# analog-out-and-pwr-amp.net
KiCad netlist of a schematic drawn in EAGLE
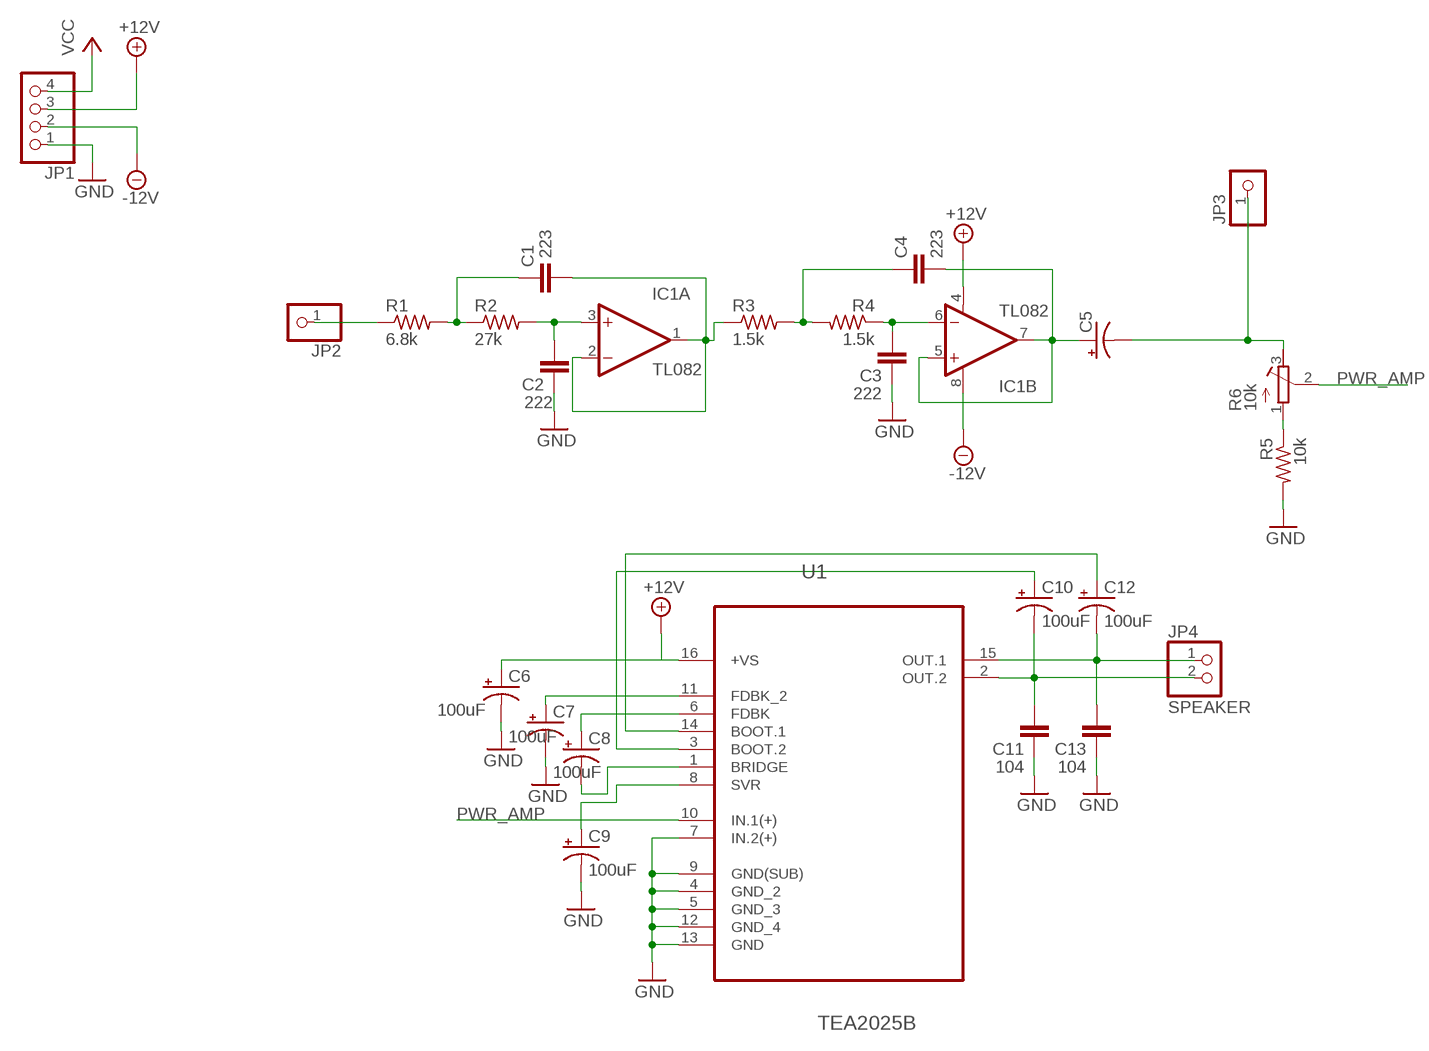
[diagram p0: schematic, sheet 1]

(export (version "E")
  (design (tool "Eeschema 10.0.6"))
  (components
    (comp (ref "C1")
      (value "223")
      (footprint "eagle-import:C025-060X050")
      (libsource (lib "eagle-import") (part "C-EUCERAMIC-CAP-COMMON"))
    )
    (comp (ref "C2")
      (value "222")
      (footprint "eagle-import:C025-060X050")
      (libsource (lib "eagle-import") (part "C-EUCERAMIC-CAP-COMMON"))
    )
    (comp (ref "C3")
      (value "222")
      (footprint "eagle-import:C025-060X050")
      (libsource (lib "eagle-import") (part "C-EUCERAMIC-CAP-COMMON"))
    )
    (comp (ref "C4")
      (value "223")
      (footprint "eagle-import:C025-060X050")
      (libsource (lib "eagle-import") (part "C-EUCERAMIC-CAP-COMMON"))
    )
    (comp (ref "C5")
      (value "CPOL-USSANYO_D")
      (footprint "eagle-import:POL-CAP-COMMON")
      (libsource (lib "eagle-import") (part "CPOL-USSANYO_D"))
    )
    (comp (ref "C6")
      (value "100uF")
      (footprint "eagle-import:POL-CAP-COMMON")
      (libsource (lib "eagle-import") (part "CPOL-USSANYO_D"))
    )
    (comp (ref "C7")
      (value "100uF")
      (footprint "eagle-import:POL-CAP-COMMON")
      (libsource (lib "eagle-import") (part "CPOL-USSANYO_D"))
    )
    (comp (ref "C8")
      (value "100uF")
      (footprint "eagle-import:POL-CAP-COMMON")
      (libsource (lib "eagle-import") (part "CPOL-USSANYO_D"))
    )
    (comp (ref "C9")
      (value "100uF")
      (footprint "eagle-import:POL-CAP-COMMON")
      (libsource (lib "eagle-import") (part "CPOL-USSANYO_D"))
    )
    (comp (ref "C10")
      (value "100uF")
      (footprint "eagle-import:POL-CAP-COMMON")
      (libsource (lib "eagle-import") (part "CPOL-USSANYO_D"))
    )
    (comp (ref "C11")
      (value "104")
      (footprint "eagle-import:C025-060X050")
      (libsource (lib "eagle-import") (part "C-EUCERAMIC-CAP-COMMON"))
    )
    (comp (ref "C12")
      (value "100uF")
      (footprint "eagle-import:POL-CAP-COMMON")
      (libsource (lib "eagle-import") (part "CPOL-USSANYO_D"))
    )
    (comp (ref "C13")
      (value "104")
      (footprint "eagle-import:C025-060X050")
      (libsource (lib "eagle-import") (part "C-EUCERAMIC-CAP-COMMON"))
    )
    (comp (ref "IC1")
      (value "TL082")
      (footprint "eagle-import:DIP08")
      (libsource (lib "eagle-import") (part "TL082"))
    )
    (comp (ref "JP1")
      (value "PINHD-1X4")
      (footprint "eagle-import:1X04")
      (libsource (lib "eagle-import") (part "PINHD-1X4"))
    )
    (comp (ref "JP2")
      (value "PINHD-1X1")
      (footprint "eagle-import:1X01")
      (libsource (lib "eagle-import") (part "PINHD-1X1"))
    )
    (comp (ref "JP3")
      (value "PINHD-1X1")
      (footprint "eagle-import:1X01")
      (libsource (lib "eagle-import") (part "PINHD-1X1"))
    )
    (comp (ref "JP4")
      (value "SPEAKER")
      (footprint "eagle-import:1X02_0.5_")
      (libsource (lib "eagle-import") (part "PINHD-1X20.5{dblquote}"))
    )
    (comp (ref "R1")
      (value "6.8k")
      (footprint "eagle-import:R-US-COMMON")
      (libsource (lib "eagle-import") (part "R-US_0207/10"))
    )
    (comp (ref "R2")
      (value "27k")
      (footprint "eagle-import:R-US-COMMON")
      (libsource (lib "eagle-import") (part "R-US_0207/10"))
    )
    (comp (ref "R3")
      (value "1.5k")
      (footprint "eagle-import:R-US-COMMON")
      (libsource (lib "eagle-import") (part "R-US_0207/10"))
    )
    (comp (ref "R4")
      (value "1.5k")
      (footprint "eagle-import:R-US-COMMON")
      (libsource (lib "eagle-import") (part "R-US_0207/10"))
    )
    (comp (ref "R5")
      (value "10k")
      (footprint "eagle-import:R-US-COMMON")
      (libsource (lib "eagle-import") (part "R-US_0207/10"))
    )
    (comp (ref "R6")
      (value "10k")
      (footprint "eagle-import:RTRIM-COMMON")
      (libsource (lib "eagle-import") (part "R-TRIMM64W"))
    )
    (comp (ref "U1")
      (value "TEA2025B")
      (footprint "eagle-import:DIP254P762X510-16")
      (libsource (lib "eagle-import") (part "TEA2025B"))
    )
  )
  (nets
    (net (code "1") (name "+12V") (class "Default")
      (node (ref "C6") (pin "+") (pinfunction "+_+") (pintype "passive"))
      (node (ref "IC1") (pin "4") (pinfunction "V-_4") (pintype "power_in"))
      (node (ref "JP1") (pin "3") (pinfunction "3_3") (pintype "passive"))
      (node (ref "U1") (pin "16") (pinfunction "+VS_16") (pintype "power_in"))
    )
    (net (code "2") (name "-12V") (class "Default")
      (node (ref "IC1") (pin "8") (pinfunction "V+_8") (pintype "power_in"))
      (node (ref "JP1") (pin "2") (pinfunction "2_2") (pintype "passive"))
    )
    (net (code "3") (name "/PWR_AMP") (class "Default")
      (node (ref "R6") (pin "2") (pinfunction "S_2") (pintype "passive"))
      (node (ref "U1") (pin "10") (pinfunction "IN.1(+)_10") (pintype "input"))
    )
    (net (code "4") (name "GND") (class "Default")
      (node (ref "C11") (pin "1") (pinfunction "1_1") (pintype "passive"))
      (node (ref "C13") (pin "1") (pinfunction "1_1") (pintype "passive"))
      (node (ref "C2") (pin "1") (pinfunction "1_1") (pintype "passive"))
      (node (ref "C3") (pin "1") (pinfunction "1_1") (pintype "passive"))
      (node (ref "C6") (pin "-") (pinfunction "-_-") (pintype "passive"))
      (node (ref "C7") (pin "-") (pinfunction "-_-") (pintype "passive"))
      (node (ref "C9") (pin "-") (pinfunction "-_-") (pintype "passive"))
      (node (ref "JP1") (pin "1") (pinfunction "1_1") (pintype "passive"))
      (node (ref "R5") (pin "2") (pinfunction "2_2") (pintype "passive"))
      (node (ref "U1") (pin "12") (pinfunction "GND_4_12") (pintype "passive"))
      (node (ref "U1") (pin "13") (pinfunction "GND_13") (pintype "passive"))
      (node (ref "U1") (pin "4") (pinfunction "GND_2_4") (pintype "passive"))
      (node (ref "U1") (pin "5") (pinfunction "GND_3_5") (pintype "passive"))
      (node (ref "U1") (pin "7") (pinfunction "IN.2(+)_7") (pintype "input"))
      (node (ref "U1") (pin "9") (pinfunction "GND(SUB)_9") (pintype "passive"))
    )
    (net (code "5") (name "Net-(C1-Pad1)") (class "Default")
      (node (ref "C1") (pin "1") (pinfunction "1_1") (pintype "passive"))
      (node (ref "R1") (pin "2") (pinfunction "2_2") (pintype "passive"))
      (node (ref "R2") (pin "1") (pinfunction "1_1") (pintype "passive"))
    )
    (net (code "6") (name "Net-(C4-Pad1)") (class "Default")
      (node (ref "C4") (pin "1") (pinfunction "1_1") (pintype "passive"))
      (node (ref "R3") (pin "2") (pinfunction "2_2") (pintype "passive"))
      (node (ref "R4") (pin "2") (pinfunction "2_2") (pintype "passive"))
    )
    (net (code "7") (name "Net-(IC1A-+IN)") (class "Default")
      (node (ref "C2") (pin "2") (pinfunction "2_2") (pintype "passive"))
      (node (ref "IC1") (pin "3") (pinfunction "+IN_3") (pintype "input"))
      (node (ref "R2") (pin "2") (pinfunction "2_2") (pintype "passive"))
    )
    (net (code "8") (name "Net-(IC1A--IN)") (class "Default")
      (node (ref "C1") (pin "2") (pinfunction "2_2") (pintype "passive"))
      (node (ref "IC1") (pin "1") (pinfunction "OUT_1") (pintype "output"))
      (node (ref "IC1") (pin "2") (pinfunction "-IN_2") (pintype "input"))
      (node (ref "R3") (pin "1") (pinfunction "1_1") (pintype "passive"))
    )
    (net (code "9") (name "Net-(IC1B-+IN)") (class "Default")
      (node (ref "C4") (pin "2") (pinfunction "2_2") (pintype "passive"))
      (node (ref "C5") (pin "+") (pinfunction "+_+") (pintype "passive"))
      (node (ref "IC1") (pin "5") (pinfunction "+IN_5") (pintype "input"))
      (node (ref "IC1") (pin "7") (pinfunction "OUT_7") (pintype "output"))
    )
    (net (code "10") (name "Net-(IC1B--IN)") (class "Default")
      (node (ref "C3") (pin "2") (pinfunction "2_2") (pintype "passive"))
      (node (ref "IC1") (pin "6") (pinfunction "-IN_6") (pintype "input"))
      (node (ref "R4") (pin "1") (pinfunction "1_1") (pintype "passive"))
    )
    (net (code "11") (name "Net-(JP2-Pad1)") (class "Default")
      (node (ref "JP2") (pin "1") (pinfunction "1_1") (pintype "passive"))
      (node (ref "R1") (pin "1") (pinfunction "1_1") (pintype "passive"))
    )
    (net (code "12") (name "Net-(R6-A)") (class "Default")
      (node (ref "R5") (pin "1") (pinfunction "1_1") (pintype "passive"))
      (node (ref "R6") (pin "1") (pinfunction "A_1") (pintype "passive"))
    )
    (net (code "13") (name "Net-(R6-E)") (class "Default")
      (node (ref "C5") (pin "-") (pinfunction "-_-") (pintype "passive"))
      (node (ref "JP3") (pin "1") (pinfunction "1_1") (pintype "passive"))
      (node (ref "R6") (pin "3") (pinfunction "E_3") (pintype "passive"))
    )
    (net (code "14") (name "Net-(U1-BOOT.1)") (class "Default")
      (node (ref "C12") (pin "+") (pinfunction "+_+") (pintype "passive"))
      (node (ref "U1") (pin "14") (pinfunction "BOOT.1_14") (pintype "passive"))
    )
    (net (code "15") (name "Net-(U1-BOOT.2)") (class "Default")
      (node (ref "C10") (pin "+") (pinfunction "+_+") (pintype "passive"))
      (node (ref "U1") (pin "3") (pinfunction "BOOT.2_3") (pintype "passive"))
    )
    (net (code "16") (name "Net-(U1-BRIDGE)") (class "Default")
      (node (ref "C8") (pin "-") (pinfunction "-_-") (pintype "passive"))
      (node (ref "U1") (pin "1") (pinfunction "BRIDGE_1") (pintype "passive"))
    )
    (net (code "17") (name "Net-(U1-FDBK)") (class "Default")
      (node (ref "C8") (pin "+") (pinfunction "+_+") (pintype "passive"))
      (node (ref "U1") (pin "6") (pinfunction "FDBK_6") (pintype "input"))
    )
    (net (code "18") (name "Net-(U1-FDBK_2)") (class "Default")
      (node (ref "C7") (pin "+") (pinfunction "+_+") (pintype "passive"))
      (node (ref "U1") (pin "11") (pinfunction "FDBK_2_11") (pintype "input"))
    )
    (net (code "19") (name "Net-(U1-OUT.1)") (class "Default")
      (node (ref "C12") (pin "-") (pinfunction "-_-") (pintype "passive"))
      (node (ref "C13") (pin "2") (pinfunction "2_2") (pintype "passive"))
      (node (ref "JP4") (pin "1") (pinfunction "1_1") (pintype "passive"))
      (node (ref "U1") (pin "15") (pinfunction "OUT.1_15") (pintype "output"))
    )
    (net (code "20") (name "Net-(U1-OUT.2)") (class "Default")
      (node (ref "C10") (pin "-") (pinfunction "-_-") (pintype "passive"))
      (node (ref "C11") (pin "2") (pinfunction "2_2") (pintype "passive"))
      (node (ref "JP4") (pin "2") (pinfunction "2_2") (pintype "passive"))
      (node (ref "U1") (pin "2") (pinfunction "OUT.2_2") (pintype "output"))
    )
    (net (code "21") (name "Net-(U1-SVR)") (class "Default")
      (node (ref "C9") (pin "+") (pinfunction "+_+") (pintype "passive"))
      (node (ref "U1") (pin "8") (pinfunction "SVR_8") (pintype "passive"))
    )
    (net (code "22") (name "VCC") (class "Default")
      (node (ref "JP1") (pin "4") (pinfunction "4_4") (pintype "passive"))
    )
  )
)
